# InkTime.net
KiCad netlist of a schematic drawn in EAGLE
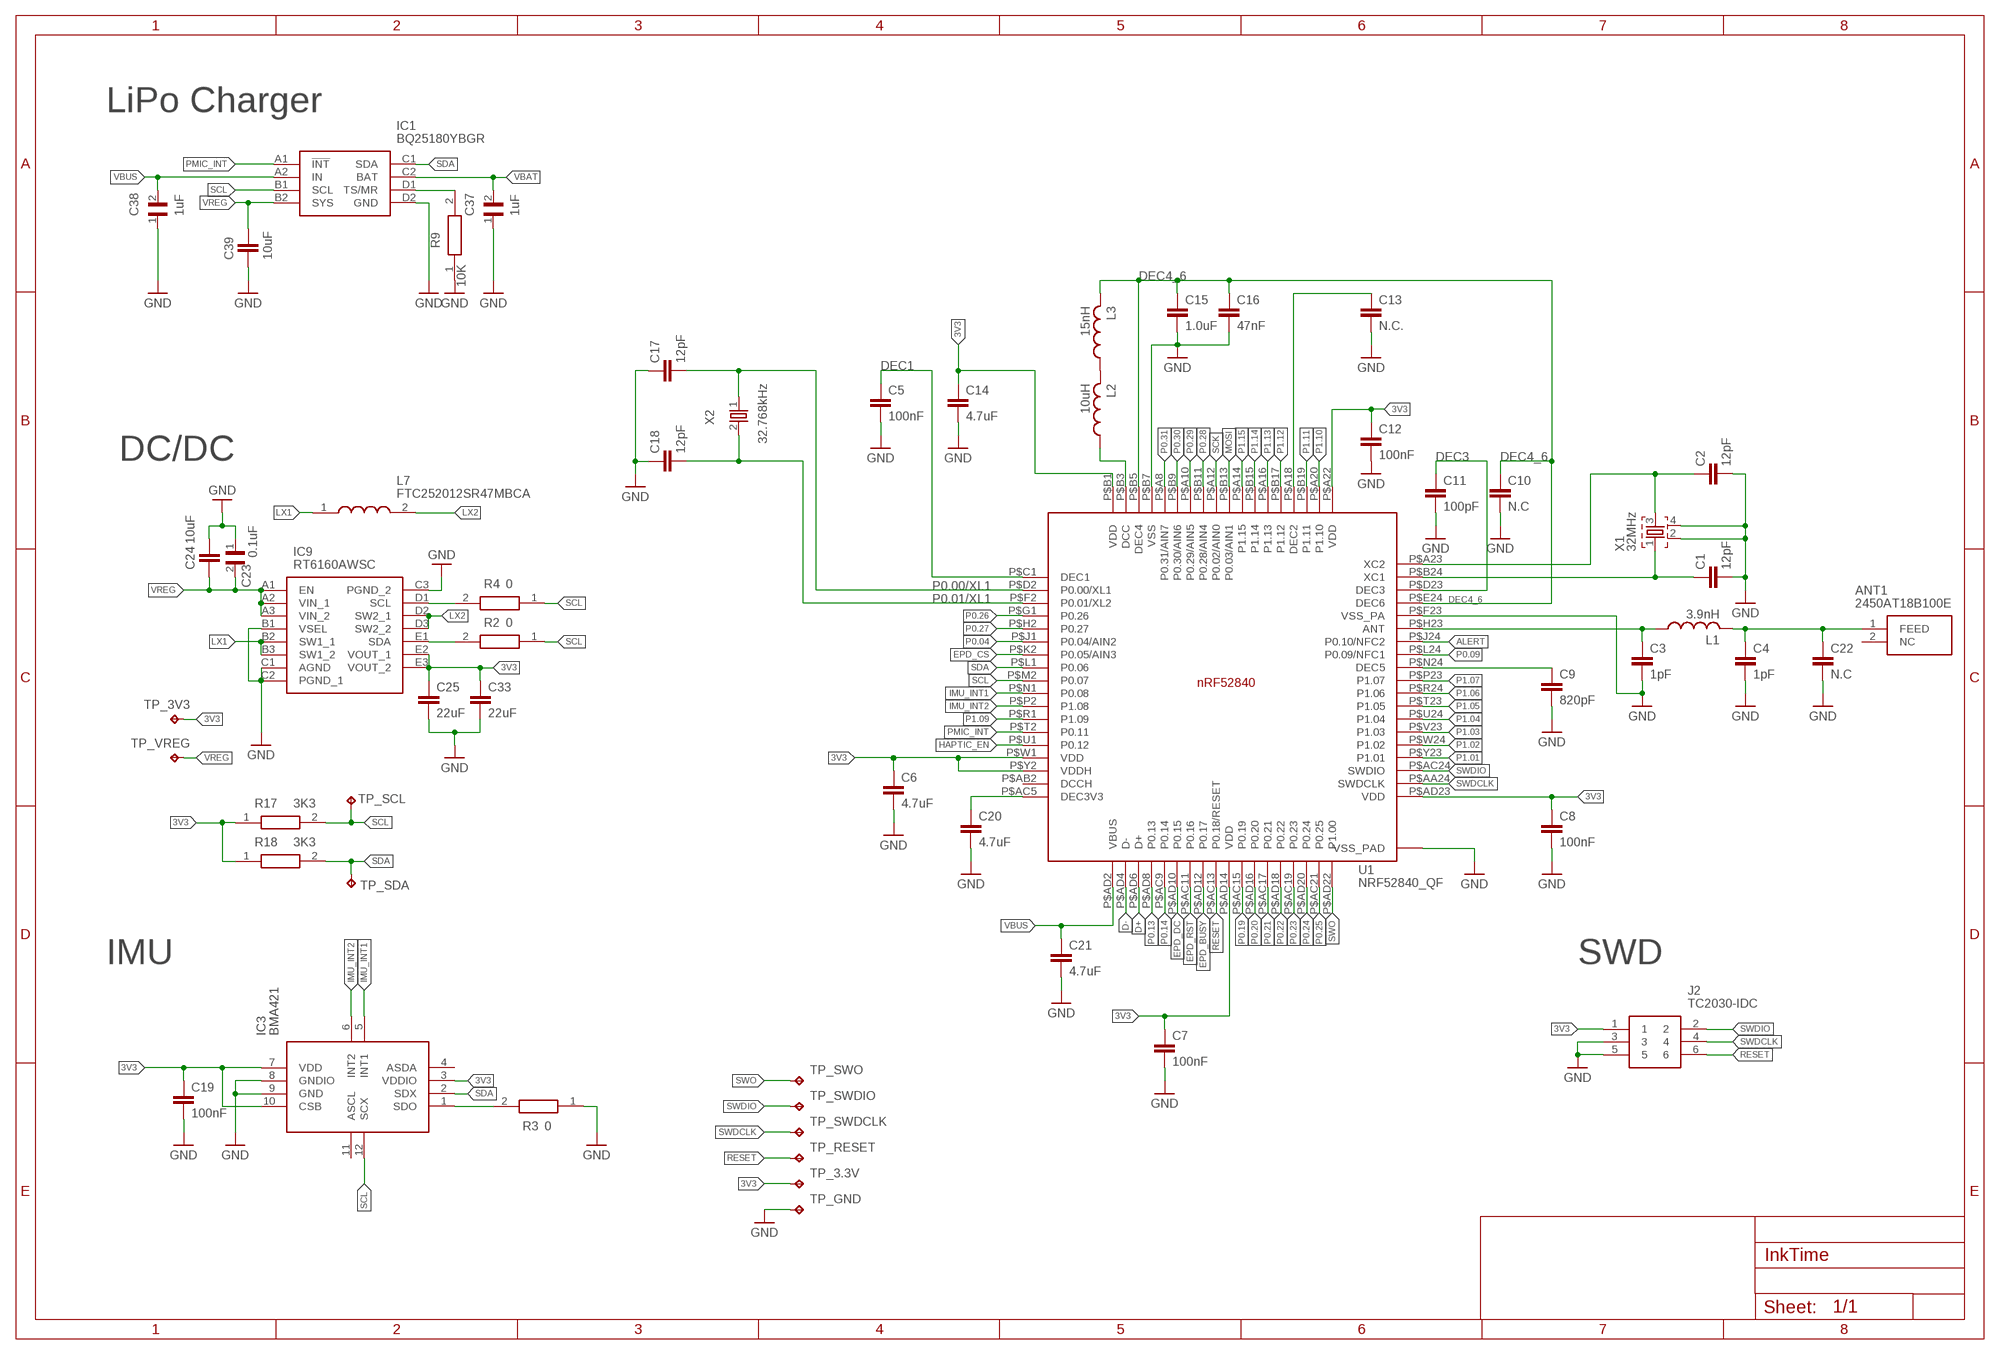
[diagram p0: schematic, sheet 1, part 1 of 2]
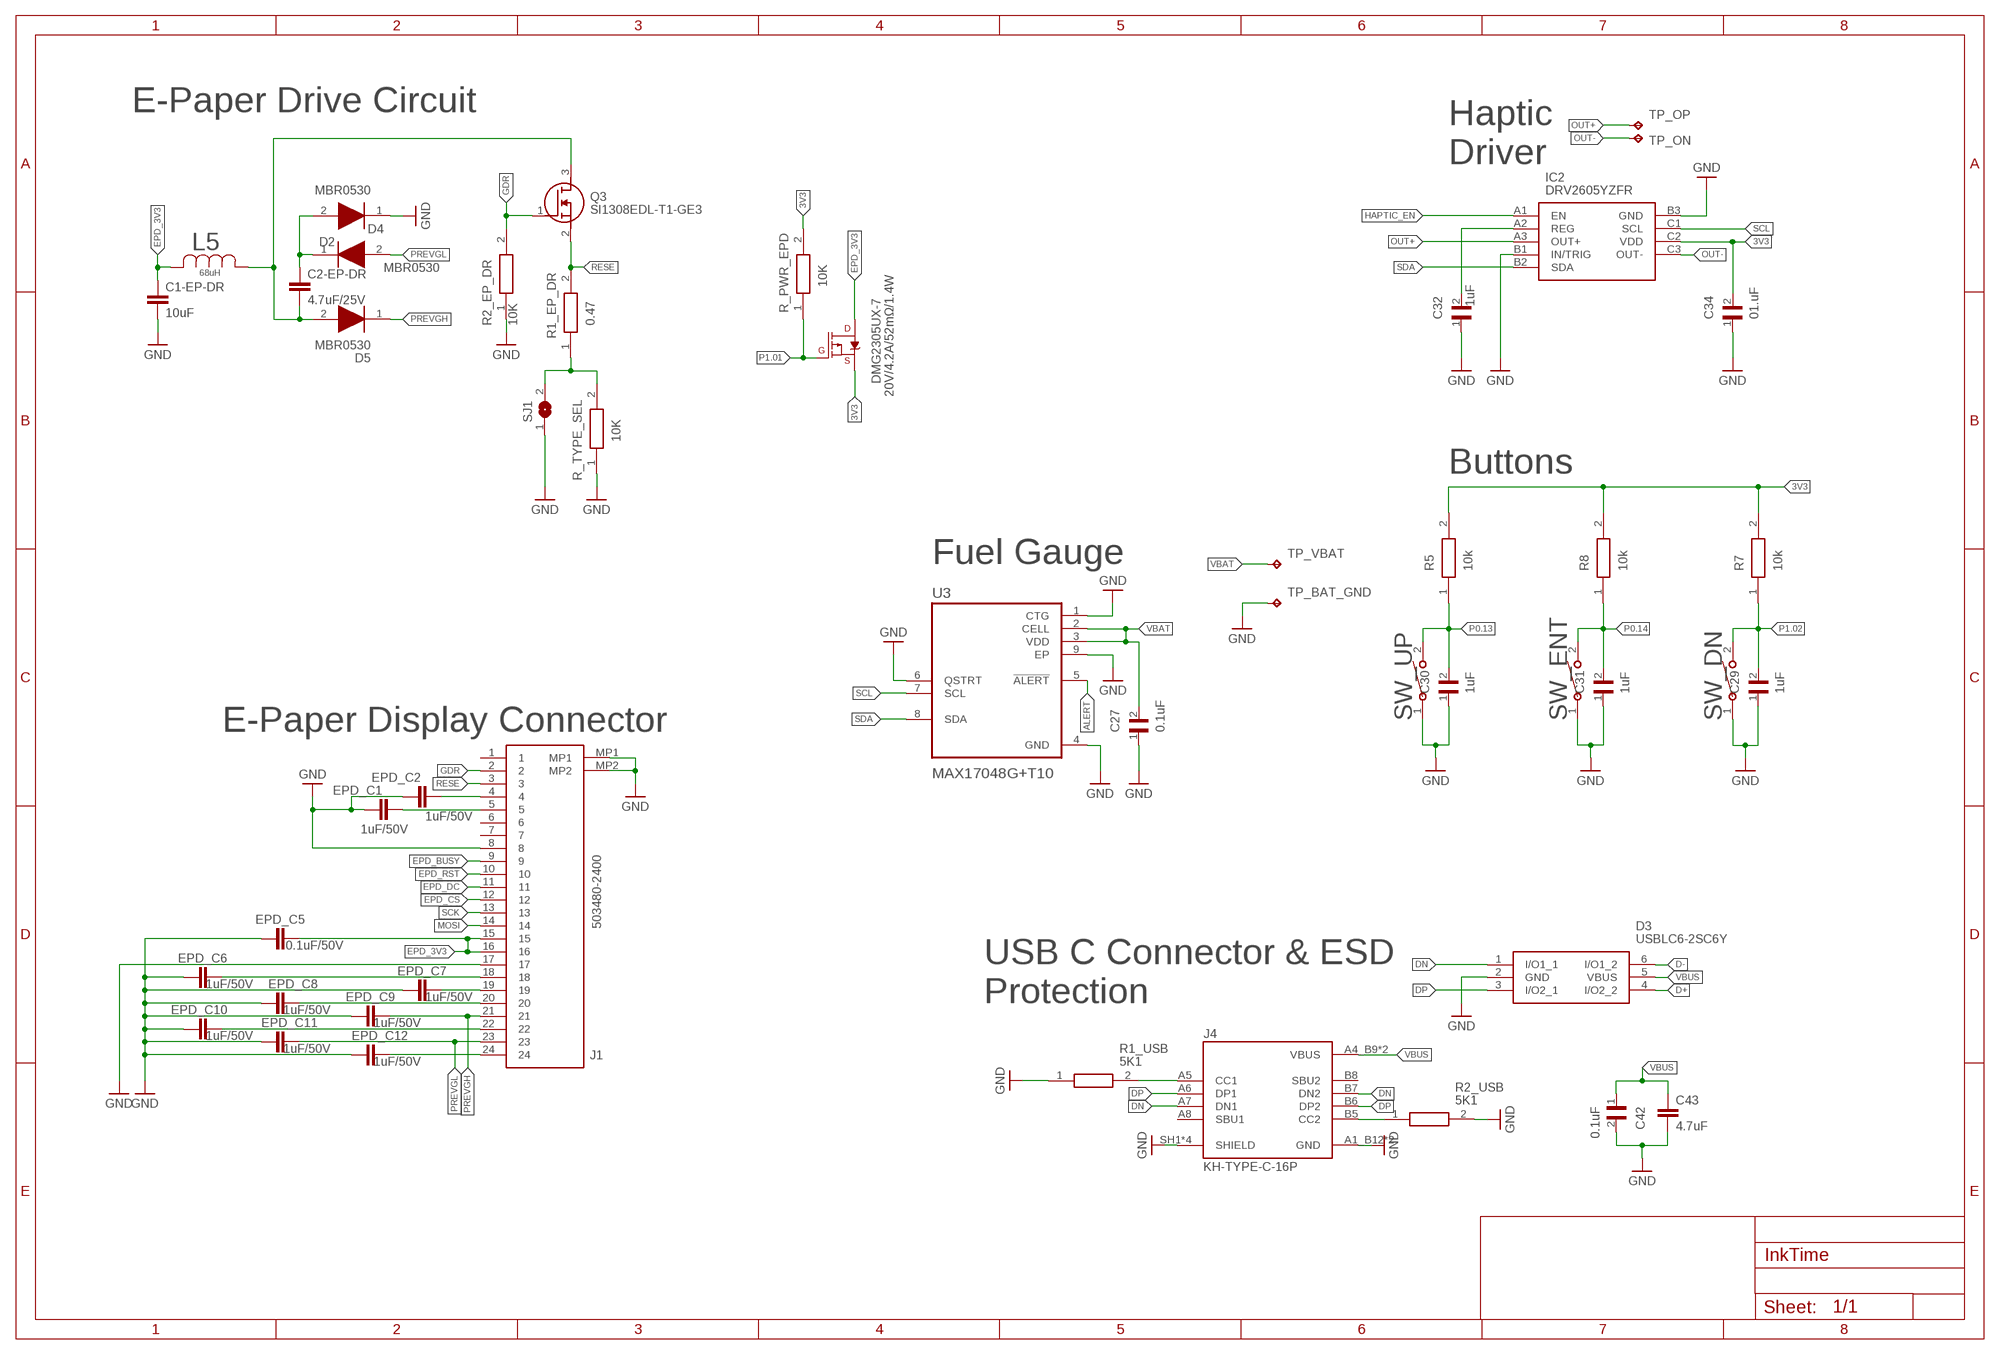
[diagram p1: schematic, sheet 1, part 2 of 2]

(export (version "E")
  (design (tool "Eeschema 10.0.6"))
  (components
    (comp (ref "ANT1")
      (value "2450AT18B100E")
      (footprint "eagle-import:2450AT18B100E_ANTC3216X140N")
      (fields (field (name "MOUSER_PART_NUMBER") "609-2450AT18B100E"))
      (libsource (lib "eagle-import") (part "2450AT18B100E_2450AT18B100E"))
    )
    (comp (ref "C1")
      (value "12pF")
      (footprint "eagle-import:NORDIC_NRF_3_RESC0201_L")
      (libsource (lib "eagle-import") (part "NORDIC_NRF_3_CAPACITOR_0201_L"))
    )
    (comp (ref "C1-EP-DR")
      (value "10uF")
      (footprint "eagle-import:NORDIC_NRF_3_RESC0402_M")
      (libsource (lib "eagle-import") (part "NORDIC_NRF_3_CAPACITOR_0402_M"))
    )
    (comp (ref "C2")
      (value "12pF")
      (footprint "eagle-import:NORDIC_NRF_3_RESC0201_L")
      (libsource (lib "eagle-import") (part "NORDIC_NRF_3_CAPACITOR_0201_L"))
    )
    (comp (ref "C2-EP-DR")
      (value "4.7uF/25V")
      (footprint "eagle-import:NORDIC_NRF_3_RESC0402_M")
      (libsource (lib "eagle-import") (part "NORDIC_NRF_3_CAPACITOR_0402_M"))
    )
    (comp (ref "C3")
      (value "1pF")
      (footprint "eagle-import:NORDIC_NRF_3_RESC0201_L")
      (libsource (lib "eagle-import") (part "NORDIC_NRF_3_CAPACITOR_0201_L"))
    )
    (comp (ref "C4")
      (value "1pF")
      (footprint "eagle-import:NORDIC_NRF_3_RESC0201_L")
      (libsource (lib "eagle-import") (part "NORDIC_NRF_3_CAPACITOR_0201_L"))
    )
    (comp (ref "C5")
      (value "100nF")
      (footprint "eagle-import:NORDIC_NRF_3_RESC0201_L")
      (libsource (lib "eagle-import") (part "NORDIC_NRF_3_CAPACITOR_0201_L"))
    )
    (comp (ref "C6")
      (value "4.7uF")
      (footprint "eagle-import:NORDIC_NRF_3_RESC0402_M")
      (libsource (lib "eagle-import") (part "NORDIC_NRF_3_CAPACITOR_0402_M"))
    )
    (comp (ref "C7")
      (value "100nF")
      (footprint "eagle-import:NORDIC_NRF_3_RESC0201_L")
      (libsource (lib "eagle-import") (part "NORDIC_NRF_3_CAPACITOR_0201_L"))
    )
    (comp (ref "C8")
      (value "100nF")
      (footprint "eagle-import:NORDIC_NRF_3_RESC0201_L")
      (libsource (lib "eagle-import") (part "NORDIC_NRF_3_CAPACITOR_0201_L"))
    )
    (comp (ref "C9")
      (value "820pF")
      (footprint "eagle-import:NORDIC_NRF_3_RESC0201_L")
      (libsource (lib "eagle-import") (part "NORDIC_NRF_3_CAPACITOR_0201_L"))
    )
    (comp (ref "C10")
      (value "N.C")
      (footprint "eagle-import:NORDIC_NRF_3_RESC0201_L")
      (libsource (lib "eagle-import") (part "NORDIC_NRF_3_CAPACITOR_0201_L"))
    )
    (comp (ref "C11")
      (value "100pF")
      (footprint "eagle-import:NORDIC_NRF_3_RESC0201_L")
      (libsource (lib "eagle-import") (part "NORDIC_NRF_3_CAPACITOR_0201_L"))
    )
    (comp (ref "C12")
      (value "100nF")
      (footprint "eagle-import:NORDIC_NRF_3_RESC0201_L")
      (libsource (lib "eagle-import") (part "NORDIC_NRF_3_CAPACITOR_0201_L"))
    )
    (comp (ref "C13")
      (value "N.C.")
      (footprint "eagle-import:NORDIC_NRF_3_RESC0201_L")
      (libsource (lib "eagle-import") (part "NORDIC_NRF_3_CAPACITOR_0201_L"))
    )
    (comp (ref "C14")
      (value "4.7uF")
      (footprint "eagle-import:NORDIC_NRF_3_RESC0402_M")
      (libsource (lib "eagle-import") (part "NORDIC_NRF_3_CAPACITOR_0402_M"))
    )
    (comp (ref "C15")
      (value "1.0uF")
      (footprint "eagle-import:NORDIC_NRF_3_RESC0402_M")
      (libsource (lib "eagle-import") (part "NORDIC_NRF_3_CAPACITOR_0402_M"))
    )
    (comp (ref "C16")
      (value "47nF")
      (footprint "eagle-import:NORDIC_NRF_3_RESC0201_L")
      (libsource (lib "eagle-import") (part "NORDIC_NRF_3_CAPACITOR_0201_L"))
    )
    (comp (ref "C17")
      (value "12pF")
      (footprint "eagle-import:NORDIC_NRF_3_RESC0201_L")
      (libsource (lib "eagle-import") (part "NORDIC_NRF_3_CAPACITOR_0201_L"))
    )
    (comp (ref "C18")
      (value "12pF")
      (footprint "eagle-import:NORDIC_NRF_3_RESC0201_L")
      (libsource (lib "eagle-import") (part "NORDIC_NRF_3_CAPACITOR_0201_L"))
    )
    (comp (ref "C19")
      (value "100nF")
      (footprint "eagle-import:NORDIC_NRF_3_RESC0201_L")
      (libsource (lib "eagle-import") (part "NORDIC_NRF_3_CAPACITOR_0201_L"))
    )
    (comp (ref "C20")
      (value "4.7uF")
      (footprint "eagle-import:NORDIC_NRF_3_RESC0402_M")
      (libsource (lib "eagle-import") (part "NORDIC_NRF_3_CAPACITOR_0402_M"))
    )
    (comp (ref "C21")
      (value "4.7uF")
      (footprint "eagle-import:NORDIC_NRF_3_RESC0402_M")
      (libsource (lib "eagle-import") (part "NORDIC_NRF_3_CAPACITOR_0402_M"))
    )
    (comp (ref "C22")
      (value "N.C")
      (footprint "eagle-import:NORDIC_NRF_3_RESC0201_L")
      (libsource (lib "eagle-import") (part "NORDIC_NRF_3_CAPACITOR_0201_L"))
    )
    (comp (ref "C23")
      (value "0.1uF")
      (footprint "eagle-import:GRM011R60J152KE01L_2_CAPC0201X13N")
      (fields (field (name "MF") "Murata") (field (name "MP") "GRM011R60J152KE01L"))
      (libsource (lib "eagle-import") (part "GRM011R60J152KE01L_2_GRM011R60J152KE01L"))
    )
    (comp (ref "C24")
      (value "10uF")
      (footprint "eagle-import:NORDIC_NRF_3_RESC0402_M")
      (libsource (lib "eagle-import") (part "NORDIC_NRF_3_CAPACITOR_0402_M"))
    )
    (comp (ref "C25")
      (value "22uF")
      (footprint "eagle-import:NORDIC_NRF_3_RESC0402_M")
      (libsource (lib "eagle-import") (part "NORDIC_NRF_3_CAPACITOR_0402_M"))
    )
    (comp (ref "C27")
      (value "0.1uF")
      (footprint "eagle-import:GRM011R60J152KE01L_1_0201")
      (libsource (lib "eagle-import") (part "GRM011R60J152KE01L_1_GRM011R60J152KE01L"))
    )
    (comp (ref "C29")
      (value "1uF")
      (footprint "eagle-import:GRM011R60J152KE01L_1_0201")
      (libsource (lib "eagle-import") (part "GRM011R60J152KE01L_1_GRM011R60J152KE01L"))
    )
    (comp (ref "C30")
      (value "1uF")
      (footprint "eagle-import:GRM011R60J152KE01L_1_0201")
      (libsource (lib "eagle-import") (part "GRM011R60J152KE01L_1_GRM011R60J152KE01L"))
    )
    (comp (ref "C31")
      (value "1uF")
      (footprint "eagle-import:GRM011R60J152KE01L_1_0201")
      (libsource (lib "eagle-import") (part "GRM011R60J152KE01L_1_GRM011R60J152KE01L"))
    )
    (comp (ref "C32")
      (value "1uF")
      (footprint "eagle-import:GRM011R60J152KE01L_1_0201")
      (libsource (lib "eagle-import") (part "GRM011R60J152KE01L_1_GRM011R60J152KE01L"))
    )
    (comp (ref "C33")
      (value "22uF")
      (footprint "eagle-import:NORDIC_NRF_3_RESC0402_M")
      (libsource (lib "eagle-import") (part "NORDIC_NRF_3_CAPACITOR_0402_M"))
    )
    (comp (ref "C34")
      (value "01.uF")
      (footprint "eagle-import:GRM011R60J152KE01L_1_0201")
      (libsource (lib "eagle-import") (part "GRM011R60J152KE01L_1_GRM011R60J152KE01L"))
    )
    (comp (ref "C37")
      (value "1uF")
      (footprint "eagle-import:GRM011R60J152KE01L_2_CAPC0201X13N")
      (fields (field (name "MF") "Murata") (field (name "MP") "GRM011R60J152KE01L"))
      (libsource (lib "eagle-import") (part "GRM011R60J152KE01L_2_GRM011R60J152KE01L"))
    )
    (comp (ref "C38")
      (value "1uF")
      (footprint "eagle-import:GRM011R60J152KE01L_2_CAPC0201X13N")
      (fields (field (name "MF") "Murata") (field (name "MP") "GRM011R60J152KE01L"))
      (libsource (lib "eagle-import") (part "GRM011R60J152KE01L_2_GRM011R60J152KE01L"))
    )
    (comp (ref "C39")
      (value "10uF")
      (footprint "eagle-import:NORDIC_NRF_3_RESC0402_M")
      (libsource (lib "eagle-import") (part "NORDIC_NRF_3_CAPACITOR_0402_M"))
    )
    (comp (ref "C42")
      (value "0.1uF")
      (footprint "eagle-import:GRM011R60J152KE01L_1_0201")
      (libsource (lib "eagle-import") (part "GRM011R60J152KE01L_1_GRM011R60J152KE01L"))
    )
    (comp (ref "C43")
      (value "4.7uF")
      (footprint "eagle-import:NORDIC_NRF_3_RESC0402_M")
      (libsource (lib "eagle-import") (part "NORDIC_NRF_3_CAPACITOR_0402_M"))
    )
    (comp (ref "D2")
      (value "MBR0530")
      (footprint "eagle-import:ESP32_C6_LIBRARY_5_SOD3716X135N")
      (fields (field (name "MF") "ON Semiconductor"))
      (libsource (lib "eagle-import") (part "ESP32_C6_LIBRARY_5_MBR0530"))
    )
    (comp (ref "D3")
      (value "USBLC6-2SC6Y")
      (footprint "eagle-import:ESP32_C6_LIBRARY_3_SOT95P280X145-6N")
      (fields (field (name "MF") "STMicroelectronics"))
      (libsource (lib "eagle-import") (part "ESP32_C6_LIBRARY_3_USBLC6-2SC6Y"))
    )
    (comp (ref "D4")
      (value "MBR0530")
      (footprint "eagle-import:ESP32_C6_LIBRARY_5_SOD3716X135N")
      (fields (field (name "MF") "ON Semiconductor"))
      (libsource (lib "eagle-import") (part "ESP32_C6_LIBRARY_5_MBR0530"))
    )
    (comp (ref "D5")
      (value "MBR0530")
      (footprint "eagle-import:ESP32_C6_LIBRARY_5_SOD3716X135N")
      (fields (field (name "MF") "ON Semiconductor"))
      (libsource (lib "eagle-import") (part "ESP32_C6_LIBRARY_5_MBR0530"))
    )
    (comp (ref "DMG2305UX-7")
      (value "20V/4.2A/52mΩ/1.4W")
      (footprint "eagle-import:ESP32_C6_LIBRARY_4_ESP32_C6_LIBRARY_4_ESP32_C6_LIBRARY_4_ESP32_C6_LIBRARY_4_ESP32_WROVER_SPARKFUN-DISCRETESEMI_SOT23-3")
      (libsource (lib "eagle-import") (part "ESP32_C6_LIBRARY_4_ESP32_WROVER_SPARKFUN-DISCRETESEMI_MOSFET_PCH-DMG2305UX-7"))
    )
    (comp (ref "EPD_C1")
      (value "1uF/50V")
      (footprint "eagle-import:NORDIC_NRF_3_RESC0402_M")
      (libsource (lib "eagle-import") (part "NORDIC_NRF_3_CAPACITOR_0402_M"))
    )
    (comp (ref "EPD_C2")
      (value "1uF/50V")
      (footprint "eagle-import:NORDIC_NRF_3_RESC0402_M")
      (libsource (lib "eagle-import") (part "NORDIC_NRF_3_CAPACITOR_0402_M"))
    )
    (comp (ref "EPD_C5")
      (value "0.1uF/50V")
      (footprint "eagle-import:NORDIC_NRF_3_RESC0201_L")
      (libsource (lib "eagle-import") (part "NORDIC_NRF_3_CAPACITOR_0201_L"))
    )
    (comp (ref "EPD_C6")
      (value "1uF/50V")
      (footprint "eagle-import:NORDIC_NRF_3_RESC0402_M")
      (libsource (lib "eagle-import") (part "NORDIC_NRF_3_CAPACITOR_0402_M"))
    )
    (comp (ref "EPD_C7")
      (value "1uF/50V")
      (footprint "eagle-import:NORDIC_NRF_3_RESC0402_M")
      (libsource (lib "eagle-import") (part "NORDIC_NRF_3_CAPACITOR_0402_M"))
    )
    (comp (ref "EPD_C8")
      (value "1uF/50V")
      (footprint "eagle-import:NORDIC_NRF_3_RESC0402_M")
      (libsource (lib "eagle-import") (part "NORDIC_NRF_3_CAPACITOR_0402_M"))
    )
    (comp (ref "EPD_C9")
      (value "1uF/50V")
      (footprint "eagle-import:NORDIC_NRF_3_RESC0402_M")
      (libsource (lib "eagle-import") (part "NORDIC_NRF_3_CAPACITOR_0402_M"))
    )
    (comp (ref "EPD_C10")
      (value "1uF/50V")
      (footprint "eagle-import:NORDIC_NRF_3_RESC0402_M")
      (libsource (lib "eagle-import") (part "NORDIC_NRF_3_CAPACITOR_0402_M"))
    )
    (comp (ref "EPD_C11")
      (value "1uF/50V")
      (footprint "eagle-import:NORDIC_NRF_3_RESC0402_M")
      (libsource (lib "eagle-import") (part "NORDIC_NRF_3_CAPACITOR_0402_M"))
    )
    (comp (ref "EPD_C12")
      (value "1uF/50V")
      (footprint "eagle-import:NORDIC_NRF_3_RESC0402_M")
      (libsource (lib "eagle-import") (part "NORDIC_NRF_3_CAPACITOR_0402_M"))
    )
    (comp (ref "IC1")
      (value "BQ25180YBGR")
      (footprint "eagle-import:BQ25180YBGR_BGA8C40P2X4_100X155X50")
      (fields (field (name "MOUSER_PART_NUMBER") "595-BQ25180YBGR"))
      (libsource (lib "eagle-import") (part "BQ25180YBGR_BQ25180YBGR"))
    )
    (comp (ref "IC2")
      (value "DRV2605YZFR")
      (footprint "eagle-import:DRV2605YZFR_BGA9C50P3X3_144X144X62")
      (libsource (lib "eagle-import") (part "DRV2605YZFR_DRV2605YZFR"))
    )
    (comp (ref "IC3")
      (value "BMA421")
      (footprint "eagle-import:BMA423_BMA423")
      (fields (field (name "ARROW_PART_NUMBER") "BMA423") (field (name "MOUSER_PART_NUMBER") "262-BMA423"))
      (libsource (lib "eagle-import") (part "BMA423_BMA423"))
    )
    (comp (ref "IC9")
      (value "RT6160AWSC")
      (footprint "eagle-import:RT6160AWSC_BGA15C40P3X5_140X230X60")
      (fields (field (name "MOUSER_PART_NUMBER") "835-RT6160AWSC"))
      (libsource (lib "eagle-import") (part "RT6160AWSC_RT6160AWSC"))
    )
    (comp (ref "J1")
      (value "503480-2400")
      (footprint "eagle-import:503480-2400_5034802400")
      (fields (field (name "MOUSER_PART_NUMBER") "538-503480-2400"))
      (libsource (lib "eagle-import") (part "503480-2400_503480-2400"))
    )
    (comp (ref "J2")
      (value "TC2030-IDC")
      (footprint "eagle-import:TC2030-IDC_TC2030IDC")
      (libsource (lib "eagle-import") (part "TC2030-IDC_TC2030-IDC"))
    )
    (comp (ref "J4")
      (value "KH-TYPE-C-16P")
      (footprint "eagle-import:KH-TYPE-C-16P_KINGHELM_KH-TYPE-C-16P")
      (fields (field (name "MF") "kinghelm"))
      (libsource (lib "eagle-import") (part "KH-TYPE-C-16P_KH-TYPE-C-16P"))
    )
    (comp (ref "L1")
      (value "3.9nH")
      (footprint "eagle-import:NORDIC_NRF_2_RESC0201_M")
      (libsource (lib "eagle-import") (part "NORDIC_NRF_2_INDUCTOR_0201_M"))
    )
    (comp (ref "L2")
      (value "10uH")
      (footprint "eagle-import:NORDIC_NRF_2_RESC0201_M")
      (libsource (lib "eagle-import") (part "NORDIC_NRF_2_INDUCTOR_0201_M"))
    )
    (comp (ref "L3")
      (value "15nH")
      (footprint "eagle-import:NORDIC_NRF_2_RESC0201_M")
      (libsource (lib "eagle-import") (part "NORDIC_NRF_2_INDUCTOR_0201_M"))
    )
    (comp (ref "L5")
      (value "68uH")
      (footprint "eagle-import:ESP32_C6_LIBRARY_2_IND_4828-WE-TPC_WRE")
      (fields
        (field (name "MANUFACTURER_PART_NUMBER") "744043680")
        (field (name "COPYRIGHT") "Copyright (C) 2024 Ultra Librarian. All rights reserved.")
      )
      (libsource (lib "eagle-import") (part "ESP32_C6_LIBRARY_2_744043680IND_4828-WE-TPC_WRE"))
    )
    (comp (ref "L7")
      (value "FTC252012SR47MBCA")
      (footprint "eagle-import:MLP2016SR47MT0S1_INDC2016X100N")
      (libsource (lib "eagle-import") (part "MLP2016SR47MT0S1_FTC252012SR47MBCA"))
    )
    (comp (ref "Q3")
      (value "SI1308EDL-T1-GE3")
      (footprint "eagle-import:ESP32_C6_LIBRARY_6_SOT65P210X110-3N")
      (fields (field (name "MF") "Vishay Siliconix"))
      (libsource (lib "eagle-import") (part "ESP32_C6_LIBRARY_6_SI1308EDL-T1-GE3"))
    )
    (comp (ref "R1_EP_DR")
      (value "0.47")
      (footprint "eagle-import:ERA-1AEB3401C_0201")
      (libsource (lib "eagle-import") (part "ERA-1AEB3401C_CPF0201D7K68C1"))
    )
    (comp (ref "R1_USB")
      (value "5K1")
      (footprint "eagle-import:ERA-1AEB3401C_0201")
      (libsource (lib "eagle-import") (part "ERA-1AEB3401C_CPF0201D7K68C1"))
    )
    (comp (ref "R2")
      (value "0")
      (footprint "eagle-import:ERA-1AEB3401C_0201")
      (libsource (lib "eagle-import") (part "ERA-1AEB3401C_CPF0201D7K68C1"))
    )
    (comp (ref "R2_EP_DR")
      (value "10K")
      (footprint "eagle-import:ERA-1AEB3401C_0201")
      (libsource (lib "eagle-import") (part "ERA-1AEB3401C_CPF0201D7K68C1"))
    )
    (comp (ref "R2_USB")
      (value "5K1")
      (footprint "eagle-import:ERA-1AEB3401C_0201")
      (libsource (lib "eagle-import") (part "ERA-1AEB3401C_CPF0201D7K68C1"))
    )
    (comp (ref "R3")
      (value "0")
      (footprint "eagle-import:ERA-1AEB3401C_0201")
      (libsource (lib "eagle-import") (part "ERA-1AEB3401C_CPF0201D7K68C1"))
    )
    (comp (ref "R4")
      (value "0")
      (footprint "eagle-import:ERA-1AEB3401C_0201")
      (libsource (lib "eagle-import") (part "ERA-1AEB3401C_CPF0201D7K68C1"))
    )
    (comp (ref "R5")
      (value "10k")
      (footprint "eagle-import:ERA-1AEB3401C_0201")
      (libsource (lib "eagle-import") (part "ERA-1AEB3401C_CPF0201D7K68C1"))
    )
    (comp (ref "R7")
      (value "10k")
      (footprint "eagle-import:ERA-1AEB3401C_0201")
      (libsource (lib "eagle-import") (part "ERA-1AEB3401C_CPF0201D7K68C1"))
    )
    (comp (ref "R8")
      (value "10k")
      (footprint "eagle-import:ERA-1AEB3401C_0201")
      (libsource (lib "eagle-import") (part "ERA-1AEB3401C_CPF0201D7K68C1"))
    )
    (comp (ref "R9")
      (value "10K")
      (footprint "eagle-import:ERA-1AEB3401C_0201")
      (libsource (lib "eagle-import") (part "ERA-1AEB3401C_CPF0201D7K68C1"))
    )
    (comp (ref "R17")
      (value "3K3")
      (footprint "eagle-import:ERA-1AEB3401C_0201")
      (libsource (lib "eagle-import") (part "ERA-1AEB3401C_CPF0201D7K68C1"))
    )
    (comp (ref "R18")
      (value "3K3")
      (footprint "eagle-import:ERA-1AEB3401C_0201")
      (libsource (lib "eagle-import") (part "ERA-1AEB3401C_CPF0201D7K68C1"))
    )
    (comp (ref "R_PWR_EPD")
      (value "10K")
      (footprint "eagle-import:ERA-1AEB3401C_0201")
      (libsource (lib "eagle-import") (part "ERA-1AEB3401C_CPF0201D7K68C1"))
    )
    (comp (ref "R_TYPE_SEL")
      (value "10K")
      (footprint "eagle-import:ERA-1AEB3401C_0201")
      (libsource (lib "eagle-import") (part "ERA-1AEB3401C_CPF0201D7K68C1"))
    )
    (comp (ref "SJ1")
      (value "ESP32_C6_LIBRARY_7_JUMPER_SJ")
      (footprint "eagle-import:ESP32_C6_LIBRARY_7_JUMPER_SJ")
      (libsource (lib "eagle-import") (part "ESP32_C6_LIBRARY_7_JUMPER_SJ"))
    )
    (comp (ref "SW_DN")
      (value "2025-10-22_07-23-44_LIBRARY_EVP-AKE31ASW_EVP-AKE31A_PAN")
      (footprint "eagle-import:2025-10-22_07-23-44_LIBRARY_SW_EVP-AKE31A_PAN")
      (fields
        (field (name "MANUFACTURER_PART_NUMBER") "EVP-AKE31A")
        (field (name "COPYRIGHT") "Copyright (C) 2025 Ultra Librarian. All rights reserved.")
      )
      (libsource (lib "eagle-import") (part "2025-10-22_07-23-44_LIBRARY_EVP-AKE31ASW_EVP-AKE31A_PAN"))
    )
    (comp (ref "SW_ENT")
      (value "2025-10-22_07-23-44_LIBRARY_EVP-AKE31ASW_EVP-AKE31A_PAN")
      (footprint "eagle-import:2025-10-22_07-23-44_LIBRARY_SW_EVP-AKE31A_PAN")
      (fields
        (field (name "MANUFACTURER_PART_NUMBER") "EVP-AKE31A")
        (field (name "COPYRIGHT") "Copyright (C) 2025 Ultra Librarian. All rights reserved.")
      )
      (libsource (lib "eagle-import") (part "2025-10-22_07-23-44_LIBRARY_EVP-AKE31ASW_EVP-AKE31A_PAN"))
    )
    (comp (ref "SW_UP")
      (value "2025-10-22_07-23-44_LIBRARY_EVP-AKE31ASW_EVP-AKE31A_PAN")
      (footprint "eagle-import:2025-10-22_07-23-44_LIBRARY_SW_EVP-AKE31A_PAN")
      (fields
        (field (name "MANUFACTURER_PART_NUMBER") "EVP-AKE31A")
        (field (name "COPYRIGHT") "Copyright (C) 2025 Ultra Librarian. All rights reserved.")
      )
      (libsource (lib "eagle-import") (part "2025-10-22_07-23-44_LIBRARY_EVP-AKE31ASW_EVP-AKE31A_PAN"))
    )
    (comp (ref "TP_3.3V")
      (value "HECTOR_WATCH_1_TPTP20R")
      (footprint "eagle-import:HECTOR_WATCH_1_TP20R")
      (libsource (lib "eagle-import") (part "HECTOR_WATCH_1_TPTP20R"))
    )
    (comp (ref "TP_3V3")
      (value "HECTOR_WATCH_1_TPTP20R")
      (footprint "eagle-import:HECTOR_WATCH_1_TP20R")
      (libsource (lib "eagle-import") (part "HECTOR_WATCH_1_TPTP20R"))
    )
    (comp (ref "TP_BAT_GND")
      (value "HECTOR_WATCH_1_TPTP20R")
      (footprint "eagle-import:HECTOR_WATCH_1_TP20R")
      (libsource (lib "eagle-import") (part "HECTOR_WATCH_1_TPTP20R"))
    )
    (comp (ref "TP_GND")
      (value "HECTOR_WATCH_1_TPTP20R")
      (footprint "eagle-import:HECTOR_WATCH_1_TP20R")
      (libsource (lib "eagle-import") (part "HECTOR_WATCH_1_TPTP20R"))
    )
    (comp (ref "TP_ON")
      (value "HECTOR_WATCH_1_TPTP20R")
      (footprint "eagle-import:HECTOR_WATCH_1_TP20R")
      (libsource (lib "eagle-import") (part "HECTOR_WATCH_1_TPTP20R"))
    )
    (comp (ref "TP_OP")
      (value "HECTOR_WATCH_1_TPTP20R")
      (footprint "eagle-import:HECTOR_WATCH_1_TP20R")
      (libsource (lib "eagle-import") (part "HECTOR_WATCH_1_TPTP20R"))
    )
    (comp (ref "TP_RESET")
      (value "HECTOR_WATCH_1_TPTP20R")
      (footprint "eagle-import:HECTOR_WATCH_1_TP20R")
      (libsource (lib "eagle-import") (part "HECTOR_WATCH_1_TPTP20R"))
    )
    (comp (ref "TP_SCL")
      (value "HECTOR_WATCH_1_TPTP20R")
      (footprint "eagle-import:HECTOR_WATCH_1_TP20R")
      (libsource (lib "eagle-import") (part "HECTOR_WATCH_1_TPTP20R"))
    )
    (comp (ref "TP_SDA")
      (value "HECTOR_WATCH_1_TPTP20R")
      (footprint "eagle-import:HECTOR_WATCH_1_TP20R")
      (libsource (lib "eagle-import") (part "HECTOR_WATCH_1_TPTP20R"))
    )
    (comp (ref "TP_SWDCLK")
      (value "HECTOR_WATCH_1_TPTP20R")
      (footprint "eagle-import:HECTOR_WATCH_1_TP20R")
      (libsource (lib "eagle-import") (part "HECTOR_WATCH_1_TPTP20R"))
    )
    (comp (ref "TP_SWDIO")
      (value "HECTOR_WATCH_1_TPTP20R")
      (footprint "eagle-import:HECTOR_WATCH_1_TP20R")
      (libsource (lib "eagle-import") (part "HECTOR_WATCH_1_TPTP20R"))
    )
    (comp (ref "TP_SWO")
      (value "HECTOR_WATCH_1_TPTP20R")
      (footprint "eagle-import:HECTOR_WATCH_1_TP20R")
      (libsource (lib "eagle-import") (part "HECTOR_WATCH_1_TPTP20R"))
    )
    (comp (ref "TP_VBAT")
      (value "HECTOR_WATCH_1_TPTP20R")
      (footprint "eagle-import:HECTOR_WATCH_1_TP20R")
      (libsource (lib "eagle-import") (part "HECTOR_WATCH_1_TPTP20R"))
    )
    (comp (ref "TP_VREG")
      (value "HECTOR_WATCH_1_TPTP20R")
      (footprint "eagle-import:HECTOR_WATCH_1_TP20R")
      (libsource (lib "eagle-import") (part "HECTOR_WATCH_1_TPTP20R"))
    )
    (comp (ref "U1")
      (value "NRF52840_QF")
      (footprint "eagle-import:NORDIC_NRF_4_AQFN50P700X700X85_HS-74N")
      (libsource (lib "eagle-import") (part "NORDIC_NRF_4_NRF52840_QF"))
    )
    (comp (ref "U3")
      (value "MAX17048G+T10")
      (footprint "eagle-import:ESP32_C6_LIBRARY_SON50P200X200X80-9N")
      (fields (field (name "MF") "Analog Devices"))
      (libsource (lib "eagle-import") (part "ESP32_C6_LIBRARY_MAX17048G+T10"))
    )
    (comp (ref "X1")
      (value "32MHz")
      (footprint "eagle-import:NORDIC_NRF_BT-XTAL_2016_N")
      (libsource (lib "eagle-import") (part "NORDIC_NRF_XTAL_32MHZ"))
    )
    (comp (ref "X2")
      (value "32.768kHz")
      (footprint "eagle-import:NORDIC_NRF_1_XTAL_3215_N")
      (libsource (lib "eagle-import") (part "NORDIC_NRF_1_XTAL_32KHZ"))
    )
  )
  (nets
    (net (code "1") (name "3V3") (class "Default")
      (node (ref "C12") (pin "1") (pinfunction "1_1") (pintype "passive"))
      (node (ref "C14") (pin "1") (pinfunction "1_1") (pintype "passive"))
      (node (ref "C19") (pin "1") (pinfunction "1_1") (pintype "passive"))
      (node (ref "C25") (pin "1") (pinfunction "1_1") (pintype "passive"))
      (node (ref "C33") (pin "1") (pinfunction "1_1") (pintype "passive"))
      (node (ref "C34") (pin "2") (pinfunction "2_2") (pintype "passive"))
      (node (ref "C6") (pin "1") (pinfunction "1_1") (pintype "passive"))
      (node (ref "C7") (pin "1") (pinfunction "1_1") (pintype "passive"))
      (node (ref "C8") (pin "1") (pinfunction "1_1") (pintype "passive"))
      (node (ref "DMG2305UX-7") (pin "2") (pinfunction "S_2") (pintype "bidirectional"))
      (node (ref "IC2") (pin "C2") (pinfunction "VDD_C2") (pintype "bidirectional"))
      (node (ref "IC3") (pin "10") (pinfunction "CSB_10") (pintype "bidirectional"))
      (node (ref "IC3") (pin "3") (pinfunction "VDDIO_3") (pintype "bidirectional"))
      (node (ref "IC3") (pin "7") (pinfunction "VDD_7") (pintype "bidirectional"))
      (node (ref "IC9") (pin "E2") (pinfunction "VOUT_1_E2") (pintype "bidirectional"))
      (node (ref "IC9") (pin "E3") (pinfunction "VOUT_2_E3") (pintype "bidirectional"))
      (node (ref "J2") (pin "1") (pinfunction "1_1") (pintype "bidirectional"))
      (node (ref "R17") (pin "1") (pinfunction "1_1") (pintype "bidirectional"))
      (node (ref "R18") (pin "1") (pinfunction "1_1") (pintype "bidirectional"))
      (node (ref "R5") (pin "2") (pinfunction "2_2") (pintype "bidirectional"))
      (node (ref "R7") (pin "2") (pinfunction "2_2") (pintype "bidirectional"))
      (node (ref "R8") (pin "2") (pinfunction "2_2") (pintype "bidirectional"))
      (node (ref "R_PWR_EPD") (pin "2") (pinfunction "2_2") (pintype "bidirectional"))
      (node (ref "TP_3.3V") (pin "TP") (pinfunction "TP_TP") (pintype "input"))
      (node (ref "TP_3V3") (pin "TP") (pinfunction "TP_TP") (pintype "input"))
      (node (ref "U1") (pin "P$A22") (pinfunction "VDD_P$A22") (pintype "power_in"))
      (node (ref "U1") (pin "P$AD14") (pinfunction "VDD_P$AD14") (pintype "power_in"))
      (node (ref "U1") (pin "P$AD23") (pinfunction "VDD_P$AD23") (pintype "power_in"))
      (node (ref "U1") (pin "P$B1") (pinfunction "VDD_P$B1") (pintype "power_in"))
      (node (ref "U1") (pin "P$W1") (pinfunction "VDD_P$W1") (pintype "power_in"))
      (node (ref "U1") (pin "P$Y2") (pinfunction "VDDH_P$Y2") (pintype "power_in"))
    )
    (net (code "2") (name "ALERT") (class "Default")
      (node (ref "U1") (pin "P$J24") (pinfunction "P0.10/NFC2_P$J24") (pintype "bidirectional"))
      (node (ref "U3") (pin "5") (pinfunction "~{ALERT}_5") (pintype "output"))
    )
    (net (code "3") (name "D+") (class "Default")
      (node (ref "D3") (pin "4") (pinfunction "I/O2_2_4") (pintype "bidirectional"))
      (node (ref "U1") (pin "P$AD6") (pinfunction "D+_P$AD6") (pintype "bidirectional"))
    )
    (net (code "4") (name "D-") (class "Default")
      (node (ref "D3") (pin "6") (pinfunction "I/O1_2_6") (pintype "bidirectional"))
      (node (ref "U1") (pin "P$AD4") (pinfunction "D-_P$AD4") (pintype "bidirectional"))
    )
    (net (code "5") (name "DN") (class "Default")
      (node (ref "D3") (pin "1") (pinfunction "I/O1_1_1") (pintype "bidirectional"))
      (node (ref "J4") (pin "A7") (pinfunction "DN1_A7") (pintype "bidirectional"))
      (node (ref "J4") (pin "B7") (pinfunction "DN2_B7") (pintype "bidirectional"))
    )
    (net (code "6") (name "DP") (class "Default")
      (node (ref "D3") (pin "3") (pinfunction "I/O2_1_3") (pintype "bidirectional"))
      (node (ref "J4") (pin "A6") (pinfunction "DP1_A6") (pintype "bidirectional"))
      (node (ref "J4") (pin "B6") (pinfunction "DP2_B6") (pintype "bidirectional"))
    )
    (net (code "7") (name "EPD_3V3") (class "Default")
      (node (ref "C1-EP-DR") (pin "1") (pinfunction "1_1") (pintype "passive"))
      (node (ref "DMG2305UX-7") (pin "3") (pinfunction "D_3") (pintype "bidirectional"))
      (node (ref "EPD_C5") (pin "2") (pinfunction "2_2") (pintype "passive"))
      (node (ref "J1") (pin "15") (pinfunction "15_15") (pintype "bidirectional"))
      (node (ref "J1") (pin "16") (pinfunction "16_16") (pintype "bidirectional"))
      (node (ref "L5") (pin "2") (pinfunction "2_2") (pintype "passive"))
    )
    (net (code "8") (name "EPD_BUSY") (class "Default")
      (node (ref "J1") (pin "9") (pinfunction "9_9") (pintype "bidirectional"))
      (node (ref "U1") (pin "P$AD12") (pinfunction "P0.17_P$AD12") (pintype "bidirectional"))
    )
    (net (code "9") (name "EPD_CS") (class "Default")
      (node (ref "J1") (pin "12") (pinfunction "12_12") (pintype "bidirectional"))
      (node (ref "U1") (pin "P$K2") (pinfunction "P0.05/AIN3_P$K2") (pintype "bidirectional"))
    )
    (net (code "10") (name "EPD_DC") (class "Default")
      (node (ref "J1") (pin "11") (pinfunction "11_11") (pintype "bidirectional"))
      (node (ref "U1") (pin "P$AD10") (pinfunction "P0.15_P$AD10") (pintype "bidirectional"))
    )
    (net (code "11") (name "EPD_RST") (class "Default")
      (node (ref "J1") (pin "10") (pinfunction "10_10") (pintype "bidirectional"))
      (node (ref "U1") (pin "P$AC11") (pinfunction "P0.16_P$AC11") (pintype "bidirectional"))
    )
    (net (code "12") (name "GDR") (class "Default")
      (node (ref "J1") (pin "2") (pinfunction "2_2") (pintype "bidirectional"))
      (node (ref "Q3") (pin "1") (pinfunction "G_1") (pintype "bidirectional"))
      (node (ref "R2_EP_DR") (pin "2") (pinfunction "2_2") (pintype "bidirectional"))
    )
    (net (code "13") (name "GND") (class "Default")
      (node (ref "C1") (pin "2") (pinfunction "2_2") (pintype "passive"))
      (node (ref "C1-EP-DR") (pin "2") (pinfunction "2_2") (pintype "passive"))
      (node (ref "C10") (pin "2") (pinfunction "2_2") (pintype "passive"))
      (node (ref "C11") (pin "2") (pinfunction "2_2") (pintype "passive"))
      (node (ref "C12") (pin "2") (pinfunction "2_2") (pintype "passive"))
      (node (ref "C13") (pin "2") (pinfunction "2_2") (pintype "passive"))
      (node (ref "C14") (pin "2") (pinfunction "2_2") (pintype "passive"))
      (node (ref "C15") (pin "2") (pinfunction "2_2") (pintype "passive"))
      (node (ref "C16") (pin "2") (pinfunction "2_2") (pintype "passive"))
      (node (ref "C17") (pin "1") (pinfunction "1_1") (pintype "passive"))
      (node (ref "C18") (pin "1") (pinfunction "1_1") (pintype "passive"))
      (node (ref "C19") (pin "2") (pinfunction "2_2") (pintype "passive"))
      (node (ref "C2") (pin "2") (pinfunction "2_2") (pintype "passive"))
      (node (ref "C20") (pin "2") (pinfunction "2_2") (pintype "passive"))
      (node (ref "C21") (pin "2") (pinfunction "2_2") (pintype "passive"))
      (node (ref "C22") (pin "2") (pinfunction "2_2") (pintype "passive"))
      (node (ref "C23") (pin "1") (pinfunction "1_1") (pintype "passive"))
      (node (ref "C24") (pin "1") (pinfunction "1_1") (pintype "passive"))
      (node (ref "C25") (pin "2") (pinfunction "2_2") (pintype "passive"))
      (node (ref "C27") (pin "1") (pinfunction "1_1") (pintype "passive"))
      (node (ref "C29") (pin "1") (pinfunction "1_1") (pintype "passive"))
      (node (ref "C3") (pin "2") (pinfunction "2_2") (pintype "passive"))
      (node (ref "C30") (pin "1") (pinfunction "1_1") (pintype "passive"))
      (node (ref "C31") (pin "1") (pinfunction "1_1") (pintype "passive"))
      (node (ref "C32") (pin "1") (pinfunction "1_1") (pintype "passive"))
      (node (ref "C33") (pin "2") (pinfunction "2_2") (pintype "passive"))
      (node (ref "C34") (pin "1") (pinfunction "1_1") (pintype "passive"))
      (node (ref "C37") (pin "1") (pinfunction "1_1") (pintype "passive"))
      (node (ref "C38") (pin "1") (pinfunction "1_1") (pintype "passive"))
      (node (ref "C39") (pin "2") (pinfunction "2_2") (pintype "passive"))
      (node (ref "C4") (pin "2") (pinfunction "2_2") (pintype "passive"))
      (node (ref "C42") (pin "2") (pinfunction "2_2") (pintype "passive"))
      (node (ref "C43") (pin "2") (pinfunction "2_2") (pintype "passive"))
      (node (ref "C5") (pin "2") (pinfunction "2_2") (pintype "passive"))
      (node (ref "C6") (pin "2") (pinfunction "2_2") (pintype "passive"))
      (node (ref "C7") (pin "2") (pinfunction "2_2") (pintype "passive"))
      (node (ref "C8") (pin "2") (pinfunction "2_2") (pintype "passive"))
      (node (ref "C9") (pin "2") (pinfunction "2_2") (pintype "passive"))
      (node (ref "D3") (pin "2") (pinfunction "GND_2") (pintype "bidirectional"))
      (node (ref "D4") (pin "1") (pinfunction "K_1") (pintype "bidirectional"))
      (node (ref "EPD_C1") (pin "1") (pinfunction "1_1") (pintype "passive"))
      (node (ref "EPD_C10") (pin "1") (pinfunction "1_1") (pintype "passive"))
      (node (ref "EPD_C11") (pin "1") (pinfunction "1_1") (pintype "passive"))
      (node (ref "EPD_C12") (pin "1") (pinfunction "1_1") (pintype "passive"))
      (node (ref "EPD_C2") (pin "1") (pinfunction "1_1") (pintype "passive"))
      (node (ref "EPD_C5") (pin "1") (pinfunction "1_1") (pintype "passive"))
      (node (ref "EPD_C6") (pin "1") (pinfunction "1_1") (pintype "passive"))
      (node (ref "EPD_C7") (pin "1") (pinfunction "1_1") (pintype "passive"))
      (node (ref "EPD_C8") (pin "1") (pinfunction "1_1") (pintype "passive"))
      (node (ref "EPD_C9") (pin "1") (pinfunction "1_1") (pintype "passive"))
      (node (ref "IC1") (pin "D2") (pinfunction "GND_D2") (pintype "bidirectional"))
      (node (ref "IC2") (pin "B1") (pinfunction "IN/TRIG_B1") (pintype "bidirectional"))
      (node (ref "IC2") (pin "B3") (pinfunction "GND_B3") (pintype "bidirectional"))
      (node (ref "IC3") (pin "8") (pinfunction "GNDIO_8") (pintype "bidirectional"))
      (node (ref "IC3") (pin "9") (pinfunction "GND_9") (pintype "bidirectional"))
      (node (ref "IC9") (pin "B1") (pinfunction "VSEL_B1") (pintype "bidirectional"))
      (node (ref "IC9") (pin "C1") (pinfunction "AGND_C1") (pintype "bidirectional"))
      (node (ref "IC9") (pin "C2") (pinfunction "PGND_1_C2") (pintype "bidirectional"))
      (node (ref "IC9") (pin "C3") (pinfunction "PGND_2_C3") (pintype "bidirectional"))
      (node (ref "J1") (pin "17") (pinfunction "17_17") (pintype "bidirectional"))
      (node (ref "J1") (pin "8") (pinfunction "8_8") (pintype "bidirectional"))
      (node (ref "J1") (pin "MP1") (pinfunction "MP1_MP1") (pintype "bidirectional"))
      (node (ref "J1") (pin "MP2") (pinfunction "MP2_MP2") (pintype "bidirectional"))
      (node (ref "J2") (pin "3") (pinfunction "3_3") (pintype "bidirectional"))
      (node (ref "J2") (pin "5") (pinfunction "5_5") (pintype "bidirectional"))
      (node (ref "J4") (pin "A12_B1") (pinfunction "GND_A12_B1") (pintype "power_in"))
      (node (ref "J4") (pin "A1_B12") (pinfunction "GND_A1_B12") (pintype "power_in"))
      (node (ref "J4") (pin "SH1") (pinfunction "SHIELD_SH1") (pintype "passive"))
      (node (ref "J4") (pin "SH2") (pinfunction "SHIELD_SH2") (pintype "passive"))
      (node (ref "J4") (pin "SH3") (pinfunction "SHIELD_SH3") (pintype "passive"))
      (node (ref "J4") (pin "SH4") (pinfunction "SHIELD_SH4") (pintype "passive"))
      (node (ref "R1_USB") (pin "1") (pinfunction "1_1") (pintype "bidirectional"))
      (node (ref "R2_EP_DR") (pin "1") (pinfunction "1_1") (pintype "bidirectional"))
      (node (ref "R2_USB") (pin "2") (pinfunction "2_2") (pintype "bidirectional"))
      (node (ref "R3") (pin "1") (pinfunction "1_1") (pintype "bidirectional"))
      (node (ref "R9") (pin "1") (pinfunction "1_1") (pintype "bidirectional"))
      (node (ref "R_TYPE_SEL") (pin "1") (pinfunction "1_1") (pintype "bidirectional"))
      (node (ref "SJ1") (pin "1") (pinfunction "1_1") (pintype "passive"))
      (node (ref "SW_DN") (pin "1") (pinfunction "1_1") (pintype "passive"))
      (node (ref "SW_ENT") (pin "1") (pinfunction "1_1") (pintype "passive"))
      (node (ref "SW_UP") (pin "1") (pinfunction "1_1") (pintype "passive"))
      (node (ref "TP_BAT_GND") (pin "TP") (pinfunction "TP_TP") (pintype "input"))
      (node (ref "TP_GND") (pin "TP") (pinfunction "TP_TP") (pintype "input"))
      (node (ref "U1") (pin "P$74") (pinfunction "VSS_PAD_P$74") (pintype "bidirectional"))
      (node (ref "U1") (pin "P$75") (pinfunction "VSS_PAD_P$75") (pintype "bidirectional"))
      (node (ref "U1") (pin "P$76") (pinfunction "VSS_PAD_P$76") (pintype "bidirectional"))
      (node (ref "U1") (pin "P$77") (pinfunction "VSS_PAD_P$77") (pintype "bidirectional"))
      (node (ref "U1") (pin "P$78") (pinfunction "VSS_PAD_P$78") (pintype "bidirectional"))
      (node (ref "U1") (pin "P$79") (pinfunction "VSS_PAD_P$79") (pintype "bidirectional"))
      (node (ref "U1") (pin "P$80") (pinfunction "VSS_PAD_P$80") (pintype "bidirectional"))
      (node (ref "U1") (pin "P$81") (pinfunction "VSS_PAD_P$81") (pintype "bidirectional"))
      (node (ref "U1") (pin "P$82") (pinfunction "VSS_PAD_P$82") (pintype "bidirectional"))
      (node (ref "U1") (pin "P$83") (pinfunction "VSS_PAD_P$83") (pintype "bidirectional"))
      (node (ref "U1") (pin "P$84") (pinfunction "VSS_PAD_P$84") (pintype "bidirectional"))
      (node (ref "U1") (pin "P$85") (pinfunction "VSS_PAD_P$85") (pintype "bidirectional"))
      (node (ref "U1") (pin "P$86") (pinfunction "VSS_PAD_P$86") (pintype "bidirectional"))
      (node (ref "U1") (pin "P$87") (pinfunction "VSS_PAD_P$87") (pintype "bidirectional"))
      (node (ref "U1") (pin "P$88") (pinfunction "VSS_PAD_P$88") (pintype "bidirectional"))
      (node (ref "U1") (pin "P$89") (pinfunction "VSS_PAD_P$89") (pintype "bidirectional"))
      (node (ref "U1") (pin "P$90") (pinfunction "VSS_PAD_P$90") (pintype "bidirectional"))
      (node (ref "U1") (pin "P$B7") (pinfunction "VSS_P$B7") (pintype "power_in"))
      (node (ref "U1") (pin "P$F23") (pinfunction "VSS_PA_P$F23") (pintype "bidirectional"))
      (node (ref "U3") (pin "1") (pinfunction "CTG_1") (pintype "power_in"))
      (node (ref "U3") (pin "4") (pinfunction "GND_4") (pintype "power_in"))
      (node (ref "U3") (pin "6") (pinfunction "QSTRT_6") (pintype "input"))
      (node (ref "U3") (pin "9") (pinfunction "EP_9") (pintype "power_in"))
      (node (ref "X1") (pin "2") (pinfunction "2_2") (pintype "passive"))
      (node (ref "X1") (pin "4") (pinfunction "4_4") (pintype "passive"))
    )
    (net (code "14") (name "HAPTIC_EN") (class "Default")
      (node (ref "IC2") (pin "A1") (pinfunction "EN_A1") (pintype "bidirectional"))
      (node (ref "U1") (pin "P$U1") (pinfunction "P0.12_P$U1") (pintype "bidirectional"))
    )
    (net (code "15") (name "IMU_INT1") (class "Default")
      (node (ref "IC3") (pin "5") (pinfunction "INT1_5") (pintype "bidirectional"))
      (node (ref "U1") (pin "P$N1") (pinfunction "P0.08_P$N1") (pintype "bidirectional"))
    )
    (net (code "16") (name "IMU_INT2") (class "Default")
      (node (ref "IC3") (pin "6") (pinfunction "INT2_6") (pintype "bidirectional"))
      (node (ref "U1") (pin "P$P2") (pinfunction "P1.08_P$P2") (pintype "bidirectional"))
    )
    (net (code "17") (name "LX1") (class "Default")
      (node (ref "IC9") (pin "B2") (pinfunction "SW1_1_B2") (pintype "bidirectional"))
      (node (ref "IC9") (pin "B3") (pinfunction "SW1_2_B3") (pintype "bidirectional"))
      (node (ref "L7") (pin "1") (pinfunction "1_1") (pintype "bidirectional"))
    )
    (net (code "18") (name "LX2") (class "Default")
      (node (ref "IC9") (pin "D2") (pinfunction "SW2_1_D2") (pintype "bidirectional"))
      (node (ref "IC9") (pin "D3") (pinfunction "SW2_2_D3") (pintype "bidirectional"))
      (node (ref "L7") (pin "2") (pinfunction "2_2") (pintype "bidirectional"))
    )
    (net (code "19") (name "MOSI") (class "Default")
      (node (ref "J1") (pin "14") (pinfunction "14_14") (pintype "bidirectional"))
      (node (ref "U1") (pin "P$B13") (pinfunction "P0.03/AIN1_P$B13") (pintype "bidirectional"))
    )
    (net (code "20") (name "Net-(ANT1-FEED)") (class "Default")
      (node (ref "ANT1") (pin "1") (pinfunction "FEED_1") (pintype "input"))
      (node (ref "C22") (pin "1") (pinfunction "1_1") (pintype "passive"))
      (node (ref "C4") (pin "1") (pinfunction "1_1") (pintype "passive"))
      (node (ref "L1") (pin "2") (pinfunction "2_2") (pintype "passive"))
    )
    (net (code "21") (name "Net-(D2-K)") (class "Default")
      (node (ref "C2-EP-DR") (pin "1") (pinfunction "1_1") (pintype "passive"))
      (node (ref "D2") (pin "1") (pinfunction "K_1") (pintype "bidirectional"))
      (node (ref "D4") (pin "2") (pinfunction "A_2") (pintype "bidirectional"))
    )
    (net (code "22") (name "Net-(D5-A)") (class "Default")
      (node (ref "C2-EP-DR") (pin "2") (pinfunction "2_2") (pintype "passive"))
      (node (ref "D5") (pin "2") (pinfunction "A_2") (pintype "bidirectional"))
      (node (ref "L5") (pin "1") (pinfunction "1_1") (pintype "passive"))
      (node (ref "Q3") (pin "3") (pinfunction "D_3") (pintype "bidirectional"))
    )
    (net (code "23") (name "Net-(EPD_C1-Pad2)") (class "Default")
      (node (ref "EPD_C1") (pin "2") (pinfunction "2_2") (pintype "passive"))
      (node (ref "J1") (pin "5") (pinfunction "5_5") (pintype "bidirectional"))
    )
    (net (code "24") (name "Net-(EPD_C2-Pad2)") (class "Default")
      (node (ref "EPD_C2") (pin "2") (pinfunction "2_2") (pintype "passive"))
      (node (ref "J1") (pin "4") (pinfunction "4_4") (pintype "bidirectional"))
    )
    (net (code "25") (name "Net-(EPD_C6-Pad2)") (class "Default")
      (node (ref "EPD_C6") (pin "2") (pinfunction "2_2") (pintype "passive"))
      (node (ref "J1") (pin "18") (pinfunction "18_18") (pintype "bidirectional"))
    )
    (net (code "26") (name "Net-(EPD_C7-Pad2)") (class "Default")
      (node (ref "EPD_C7") (pin "2") (pinfunction "2_2") (pintype "passive"))
      (node (ref "J1") (pin "19") (pinfunction "19_19") (pintype "bidirectional"))
    )
    (net (code "27") (name "Net-(EPD_C8-Pad2)") (class "Default")
      (node (ref "EPD_C8") (pin "2") (pinfunction "2_2") (pintype "passive"))
      (node (ref "J1") (pin "20") (pinfunction "20_20") (pintype "bidirectional"))
    )
    (net (code "28") (name "Net-(EPD_C10-Pad2)") (class "Default")
      (node (ref "EPD_C10") (pin "2") (pinfunction "2_2") (pintype "passive"))
      (node (ref "J1") (pin "22") (pinfunction "22_22") (pintype "bidirectional"))
    )
    (net (code "29") (name "Net-(EPD_C12-Pad2)") (class "Default")
      (node (ref "EPD_C12") (pin "2") (pinfunction "2_2") (pintype "passive"))
      (node (ref "J1") (pin "24") (pinfunction "24_24") (pintype "bidirectional"))
    )
    (net (code "30") (name "Net-(IC1-TS{slash}MR)") (class "Default")
      (node (ref "IC1") (pin "D1") (pinfunction "TS/MR_D1") (pintype "bidirectional"))
      (node (ref "R9") (pin "2") (pinfunction "2_2") (pintype "bidirectional"))
    )
    (net (code "31") (name "Net-(IC2-REG)") (class "Default")
      (node (ref "C32") (pin "2") (pinfunction "2_2") (pintype "passive"))
      (node (ref "IC2") (pin "A2") (pinfunction "REG_A2") (pintype "bidirectional"))
    )
    (net (code "32") (name "Net-(IC3-SDO)") (class "Default")
      (node (ref "IC3") (pin "1") (pinfunction "SDO_1") (pintype "bidirectional"))
      (node (ref "R3") (pin "2") (pinfunction "2_2") (pintype "bidirectional"))
    )
    (net (code "33") (name "Net-(IC9-SCL)") (class "Default")
      (node (ref "IC9") (pin "D1") (pinfunction "SCL_D1") (pintype "bidirectional"))
      (node (ref "R4") (pin "2") (pinfunction "2_2") (pintype "bidirectional"))
    )
    (net (code "34") (name "Net-(IC9-SDA)") (class "Default")
      (node (ref "IC9") (pin "E1") (pinfunction "SDA_E1") (pintype "bidirectional"))
      (node (ref "R2") (pin "2") (pinfunction "2_2") (pintype "bidirectional"))
    )
    (net (code "35") (name "Net-(J4-CC1)") (class "Default")
      (node (ref "J4") (pin "A5") (pinfunction "CC1_A5") (pintype "bidirectional"))
      (node (ref "R1_USB") (pin "2") (pinfunction "2_2") (pintype "bidirectional"))
    )
    (net (code "36") (name "Net-(J4-CC2)") (class "Default")
      (node (ref "J4") (pin "B5") (pinfunction "CC2_B5") (pintype "bidirectional"))
      (node (ref "R2_USB") (pin "1") (pinfunction "1_1") (pintype "bidirectional"))
    )
    (net (code "37") (name "Net-(L2-Pad2)") (class "Default")
      (node (ref "L2") (pin "2") (pinfunction "2_2") (pintype "passive"))
      (node (ref "L3") (pin "1") (pinfunction "1_1") (pintype "passive"))
    )
    (net (code "38") (name "Net-(R1_EP_DR-Pad1)") (class "Default")
      (node (ref "R1_EP_DR") (pin "1") (pinfunction "1_1") (pintype "bidirectional"))
      (node (ref "R_TYPE_SEL") (pin "2") (pinfunction "2_2") (pintype "bidirectional"))
      (node (ref "SJ1") (pin "2") (pinfunction "2_2") (pintype "passive"))
    )
    (net (code "39") (name "Net-(U1-ANT)") (class "Default")
      (node (ref "C3") (pin "1") (pinfunction "1_1") (pintype "passive"))
      (node (ref "L1") (pin "1") (pinfunction "1_1") (pintype "passive"))
      (node (ref "U1") (pin "P$H23") (pinfunction "ANT_P$H23") (pintype "bidirectional"))
    )
    (net (code "40") (name "Net-(U1-DCC)") (class "Default")
      (node (ref "L2") (pin "1") (pinfunction "1_1") (pintype "passive"))
      (node (ref "U1") (pin "P$B3") (pinfunction "DCC_P$B3") (pintype "output"))
    )
    (net (code "41") (name "Net-(U1-DEC1)") (class "Default")
      (node (ref "C5") (pin "1") (pinfunction "1_1") (pintype "passive"))
      (node (ref "U1") (pin "P$C1") (pinfunction "DEC1_P$C1") (pintype "power_in"))
    )
    (net (code "42") (name "Net-(U1-DEC2)") (class "Default")
      (node (ref "C13") (pin "1") (pinfunction "1_1") (pintype "passive"))
      (node (ref "U1") (pin "P$A18") (pinfunction "DEC2_P$A18") (pintype "bidirectional"))
    )
    (net (code "43") (name "Net-(U1-DEC3)") (class "Default")
      (node (ref "C11") (pin "1") (pinfunction "1_1") (pintype "passive"))
      (node (ref "U1") (pin "P$D23") (pinfunction "DEC3_P$D23") (pintype "bidirectional"))
    )
    (net (code "44") (name "Net-(U1-DEC3V3)") (class "Default")
      (node (ref "C20") (pin "1") (pinfunction "1_1") (pintype "passive"))
      (node (ref "U1") (pin "P$AC5") (pinfunction "DEC3V3_P$AC5") (pintype "bidirectional"))
    )
    (net (code "45") (name "Net-(U1-DEC4)") (class "Default")
      (node (ref "C10") (pin "1") (pinfunction "1_1") (pintype "passive"))
      (node (ref "C15") (pin "1") (pinfunction "1_1") (pintype "passive"))
      (node (ref "C16") (pin "1") (pinfunction "1_1") (pintype "passive"))
      (node (ref "L3") (pin "2") (pinfunction "2_2") (pintype "passive"))
      (node (ref "U1") (pin "P$B5") (pinfunction "DEC4_P$B5") (pintype "power_in"))
      (node (ref "U1") (pin "P$E24") (pinfunction "DEC6_P$E24") (pintype "bidirectional"))
    )
    (net (code "46") (name "Net-(U1-DEC5)") (class "Default")
      (node (ref "C9") (pin "1") (pinfunction "1_1") (pintype "passive"))
      (node (ref "U1") (pin "P$N24") (pinfunction "DEC5_P$N24") (pintype "bidirectional"))
    )
    (net (code "47") (name "Net-(U1-P0.00{slash}XL1)") (class "Default")
      (node (ref "C17") (pin "2") (pinfunction "2_2") (pintype "passive"))
      (node (ref "U1") (pin "P$D2") (pinfunction "P0.00/XL1_P$D2") (pintype "bidirectional"))
      (node (ref "X2") (pin "1") (pinfunction "1_1") (pintype "passive"))
    )
    (net (code "48") (name "Net-(U1-P0.01{slash}XL2)") (class "Default")
      (node (ref "C18") (pin "2") (pinfunction "2_2") (pintype "passive"))
      (node (ref "U1") (pin "P$F2") (pinfunction "P0.01/XL2_P$F2") (pintype "bidirectional"))
      (node (ref "X2") (pin "2") (pinfunction "2_2") (pintype "passive"))
    )
    (net (code "49") (name "Net-(U1-XC1)") (class "Default")
      (node (ref "C1") (pin "1") (pinfunction "1_1") (pintype "passive"))
      (node (ref "U1") (pin "P$B24") (pinfunction "XC1_P$B24") (pintype "input"))
      (node (ref "X1") (pin "1") (pinfunction "1_1") (pintype "passive"))
    )
    (net (code "50") (name "Net-(U1-XC2)") (class "Default")
      (node (ref "C2") (pin "1") (pinfunction "1_1") (pintype "passive"))
      (node (ref "U1") (pin "P$A23") (pinfunction "XC2_P$A23") (pintype "output"))
      (node (ref "X1") (pin "3") (pinfunction "3_3") (pintype "passive"))
    )
    (net (code "51") (name "OUT+") (class "Default")
      (node (ref "IC2") (pin "A3") (pinfunction "OUT+_A3") (pintype "bidirectional"))
      (node (ref "TP_OP") (pin "TP") (pinfunction "TP_TP") (pintype "input"))
    )
    (net (code "52") (name "OUT-") (class "Default")
      (node (ref "IC2") (pin "C3") (pinfunction "OUT-_C3") (pintype "bidirectional"))
      (node (ref "TP_ON") (pin "TP") (pinfunction "TP_TP") (pintype "input"))
    )
    (net (code "53") (name "P0.04") (class "Default")
      (node (ref "U1") (pin "P$J1") (pinfunction "P0.04/AIN2_P$J1") (pintype "bidirectional"))
    )
    (net (code "54") (name "P0.09") (class "Default")
      (node (ref "U1") (pin "P$L24") (pinfunction "P0.09/NFC1_P$L24") (pintype "bidirectional"))
    )
    (net (code "55") (name "P0.13") (class "Default")
      (node (ref "C30") (pin "2") (pinfunction "2_2") (pintype "passive"))
      (node (ref "R5") (pin "1") (pinfunction "1_1") (pintype "bidirectional"))
      (node (ref "SW_UP") (pin "2") (pinfunction "2_2") (pintype "passive"))
      (node (ref "U1") (pin "P$AD8") (pinfunction "P0.13_P$AD8") (pintype "bidirectional"))
    )
    (net (code "56") (name "P0.14") (class "Default")
      (node (ref "C31") (pin "2") (pinfunction "2_2") (pintype "passive"))
      (node (ref "R8") (pin "1") (pinfunction "1_1") (pintype "bidirectional"))
      (node (ref "SW_ENT") (pin "2") (pinfunction "2_2") (pintype "passive"))
      (node (ref "U1") (pin "P$AC9") (pinfunction "P0.14_P$AC9") (pintype "bidirectional"))
    )
    (net (code "57") (name "P0.19") (class "Default")
      (node (ref "U1") (pin "P$AC15") (pinfunction "P0.19_P$AC15") (pintype "bidirectional"))
    )
    (net (code "58") (name "P0.20") (class "Default")
      (node (ref "U1") (pin "P$AD16") (pinfunction "P0.20_P$AD16") (pintype "bidirectional"))
    )
    (net (code "59") (name "P0.21") (class "Default")
      (node (ref "U1") (pin "P$AC17") (pinfunction "P0.21_P$AC17") (pintype "bidirectional"))
    )
    (net (code "60") (name "P0.22") (class "Default")
      (node (ref "U1") (pin "P$AD18") (pinfunction "P0.22_P$AD18") (pintype "bidirectional"))
    )
    (net (code "61") (name "P0.23") (class "Default")
      (node (ref "U1") (pin "P$AC19") (pinfunction "P0.23_P$AC19") (pintype "bidirectional"))
    )
    (net (code "62") (name "P0.24") (class "Default")
      (node (ref "U1") (pin "P$AD20") (pinfunction "P0.24_P$AD20") (pintype "bidirectional"))
    )
    (net (code "63") (name "P0.25") (class "Default")
      (node (ref "U1") (pin "P$AC21") (pinfunction "P0.25_P$AC21") (pintype "bidirectional"))
    )
    (net (code "64") (name "P0.26") (class "Default")
      (node (ref "U1") (pin "P$G1") (pinfunction "P0.26_P$G1") (pintype "bidirectional"))
    )
    (net (code "65") (name "P0.27") (class "Default")
      (node (ref "U1") (pin "P$H2") (pinfunction "P0.27_P$H2") (pintype "bidirectional"))
    )
    (net (code "66") (name "P0.28") (class "Default")
      (node (ref "U1") (pin "P$B11") (pinfunction "P0.28/AIN4_P$B11") (pintype "bidirectional"))
    )
    (net (code "67") (name "P0.29") (class "Default")
      (node (ref "U1") (pin "P$A10") (pinfunction "P0.29/AIN5_P$A10") (pintype "bidirectional"))
    )
    (net (code "68") (name "P0.30") (class "Default")
      (node (ref "U1") (pin "P$B9") (pinfunction "P0.30/AIN6_P$B9") (pintype "bidirectional"))
    )
    (net (code "69") (name "P0.31") (class "Default")
      (node (ref "U1") (pin "P$A8") (pinfunction "P0.31/AIN7_P$A8") (pintype "bidirectional"))
    )
    (net (code "70") (name "P1.01") (class "Default")
      (node (ref "DMG2305UX-7") (pin "1") (pinfunction "G_1") (pintype "bidirectional"))
      (node (ref "R_PWR_EPD") (pin "1") (pinfunction "1_1") (pintype "bidirectional"))
      (node (ref "U1") (pin "P$Y23") (pinfunction "P1.01_P$Y23") (pintype "bidirectional"))
    )
    (net (code "71") (name "P1.02") (class "Default")
      (node (ref "C29") (pin "2") (pinfunction "2_2") (pintype "passive"))
      (node (ref "R7") (pin "1") (pinfunction "1_1") (pintype "bidirectional"))
      (node (ref "SW_DN") (pin "2") (pinfunction "2_2") (pintype "passive"))
      (node (ref "U1") (pin "P$W24") (pinfunction "P1.02_P$W24") (pintype "bidirectional"))
    )
    (net (code "72") (name "P1.03") (class "Default")
      (node (ref "U1") (pin "P$V23") (pinfunction "P1.03_P$V23") (pintype "bidirectional"))
    )
    (net (code "73") (name "P1.04") (class "Default")
      (node (ref "U1") (pin "P$U24") (pinfunction "P1.04_P$U24") (pintype "bidirectional"))
    )
    (net (code "74") (name "P1.05") (class "Default")
      (node (ref "U1") (pin "P$T23") (pinfunction "P1.05_P$T23") (pintype "bidirectional"))
    )
    (net (code "75") (name "P1.06") (class "Default")
      (node (ref "U1") (pin "P$R24") (pinfunction "P1.06_P$R24") (pintype "bidirectional"))
    )
    (net (code "76") (name "P1.07") (class "Default")
      (node (ref "U1") (pin "P$P23") (pinfunction "P1.07_P$P23") (pintype "bidirectional"))
    )
    (net (code "77") (name "P1.09") (class "Default")
      (node (ref "U1") (pin "P$R1") (pinfunction "P1.09_P$R1") (pintype "bidirectional"))
    )
    (net (code "78") (name "P1.10") (class "Default")
      (node (ref "U1") (pin "P$A20") (pinfunction "P1.10_P$A20") (pintype "bidirectional"))
    )
    (net (code "79") (name "P1.11") (class "Default")
      (node (ref "U1") (pin "P$B19") (pinfunction "P1.11_P$B19") (pintype "bidirectional"))
    )
    (net (code "80") (name "P1.12") (class "Default")
      (node (ref "U1") (pin "P$B17") (pinfunction "P1.12_P$B17") (pintype "bidirectional"))
    )
    (net (code "81") (name "P1.13") (class "Default")
      (node (ref "U1") (pin "P$A16") (pinfunction "P1.13_P$A16") (pintype "bidirectional"))
    )
    (net (code "82") (name "P1.14") (class "Default")
      (node (ref "U1") (pin "P$B15") (pinfunction "P1.14_P$B15") (pintype "bidirectional"))
    )
    (net (code "83") (name "P1.15") (class "Default")
      (node (ref "U1") (pin "P$A14") (pinfunction "P1.15_P$A14") (pintype "bidirectional"))
    )
    (net (code "84") (name "PMIC_INT") (class "Default")
      (node (ref "IC1") (pin "A1") (pinfunction "~{INT}_A1") (pintype "bidirectional"))
      (node (ref "U1") (pin "P$T2") (pinfunction "P0.11_P$T2") (pintype "bidirectional"))
    )
    (net (code "85") (name "PREVGH") (class "Default")
      (node (ref "D5") (pin "1") (pinfunction "K_1") (pintype "bidirectional"))
      (node (ref "EPD_C9") (pin "2") (pinfunction "2_2") (pintype "passive"))
      (node (ref "J1") (pin "21") (pinfunction "21_21") (pintype "bidirectional"))
    )
    (net (code "86") (name "PREVGL") (class "Default")
      (node (ref "D2") (pin "2") (pinfunction "A_2") (pintype "bidirectional"))
      (node (ref "EPD_C11") (pin "2") (pinfunction "2_2") (pintype "passive"))
      (node (ref "J1") (pin "23") (pinfunction "23_23") (pintype "bidirectional"))
    )
    (net (code "87") (name "RESE") (class "Default")
      (node (ref "J1") (pin "3") (pinfunction "3_3") (pintype "bidirectional"))
      (node (ref "Q3") (pin "2") (pinfunction "S_2") (pintype "bidirectional"))
      (node (ref "R1_EP_DR") (pin "2") (pinfunction "2_2") (pintype "bidirectional"))
    )
    (net (code "88") (name "RESET") (class "Default")
      (node (ref "J2") (pin "6") (pinfunction "6_6") (pintype "bidirectional"))
      (node (ref "TP_RESET") (pin "TP") (pinfunction "TP_TP") (pintype "input"))
      (node (ref "U1") (pin "P$AC13") (pinfunction "P0.18/RESET_P$AC13") (pintype "bidirectional"))
    )
    (net (code "89") (name "SCK") (class "Default")
      (node (ref "J1") (pin "13") (pinfunction "13_13") (pintype "bidirectional"))
      (node (ref "U1") (pin "P$A12") (pinfunction "P0.02/AIN0_P$A12") (pintype "bidirectional"))
    )
    (net (code "90") (name "SCL") (class "Default")
      (node (ref "IC1") (pin "B1") (pinfunction "SCL_B1") (pintype "bidirectional"))
      (node (ref "IC2") (pin "C1") (pinfunction "SCL_C1") (pintype "bidirectional"))
      (node (ref "IC3") (pin "12") (pinfunction "SCX_12") (pintype "bidirectional"))
      (node (ref "R17") (pin "2") (pinfunction "2_2") (pintype "bidirectional"))
      (node (ref "R2") (pin "1") (pinfunction "1_1") (pintype "bidirectional"))
      (node (ref "R4") (pin "1") (pinfunction "1_1") (pintype "bidirectional"))
      (node (ref "TP_SCL") (pin "TP") (pinfunction "TP_TP") (pintype "input"))
      (node (ref "U1") (pin "P$M2") (pinfunction "P0.07_P$M2") (pintype "bidirectional"))
      (node (ref "U3") (pin "7") (pinfunction "SCL_7") (pintype "input"))
    )
    (net (code "91") (name "SDA") (class "Default")
      (node (ref "IC1") (pin "C1") (pinfunction "SDA_C1") (pintype "bidirectional"))
      (node (ref "IC2") (pin "B2") (pinfunction "SDA_B2") (pintype "bidirectional"))
      (node (ref "IC3") (pin "2") (pinfunction "SDX_2") (pintype "bidirectional"))
      (node (ref "R18") (pin "2") (pinfunction "2_2") (pintype "bidirectional"))
      (node (ref "TP_SDA") (pin "TP") (pinfunction "TP_TP") (pintype "input"))
      (node (ref "U1") (pin "P$L1") (pinfunction "P0.06_P$L1") (pintype "bidirectional"))
      (node (ref "U3") (pin "8") (pinfunction "SDA_8") (pintype "bidirectional"))
    )
    (net (code "92") (name "SWDCLK") (class "Default")
      (node (ref "J2") (pin "4") (pinfunction "4_4") (pintype "bidirectional"))
      (node (ref "TP_SWDCLK") (pin "TP") (pinfunction "TP_TP") (pintype "input"))
      (node (ref "U1") (pin "P$AA24") (pinfunction "SWDCLK_P$AA24") (pintype "input"))
    )
    (net (code "93") (name "SWDIO") (class "Default")
      (node (ref "J2") (pin "2") (pinfunction "2_2") (pintype "bidirectional"))
      (node (ref "TP_SWDIO") (pin "TP") (pinfunction "TP_TP") (pintype "input"))
      (node (ref "U1") (pin "P$AC24") (pinfunction "SWDIO_P$AC24") (pintype "bidirectional"))
    )
    (net (code "94") (name "SWO") (class "Default")
      (node (ref "TP_SWO") (pin "TP") (pinfunction "TP_TP") (pintype "input"))
      (node (ref "U1") (pin "P$AD22") (pinfunction "P1.00_P$AD22") (pintype "bidirectional"))
    )
    (net (code "95") (name "VBAT") (class "Default")
      (node (ref "C27") (pin "2") (pinfunction "2_2") (pintype "passive"))
      (node (ref "C37") (pin "2") (pinfunction "2_2") (pintype "passive"))
      (node (ref "IC1") (pin "C2") (pinfunction "BAT_C2") (pintype "bidirectional"))
      (node (ref "TP_VBAT") (pin "TP") (pinfunction "TP_TP") (pintype "input"))
      (node (ref "U3") (pin "2") (pinfunction "CELL_2") (pintype "power_in"))
      (node (ref "U3") (pin "3") (pinfunction "VDD_3") (pintype "power_in"))
    )
    (net (code "96") (name "VBUS") (class "Default")
      (node (ref "C21") (pin "1") (pinfunction "1_1") (pintype "passive"))
      (node (ref "C38") (pin "2") (pinfunction "2_2") (pintype "passive"))
      (node (ref "C42") (pin "1") (pinfunction "1_1") (pintype "passive"))
      (node (ref "C43") (pin "1") (pinfunction "1_1") (pintype "passive"))
      (node (ref "D3") (pin "5") (pinfunction "VBUS_5") (pintype "bidirectional"))
      (node (ref "IC1") (pin "A2") (pinfunction "IN_A2") (pintype "bidirectional"))
      (node (ref "J4") (pin "A4_B9") (pinfunction "VBUS_A4_B9") (pintype "power_in"))
      (node (ref "J4") (pin "A9_B4") (pinfunction "VBUS_A9_B4") (pintype "power_in"))
      (node (ref "U1") (pin "P$AD2") (pinfunction "VBUS_P$AD2") (pintype "power_in"))
    )
    (net (code "97") (name "VREG") (class "Default")
      (node (ref "C23") (pin "2") (pinfunction "2_2") (pintype "passive"))
      (node (ref "C24") (pin "2") (pinfunction "2_2") (pintype "passive"))
      (node (ref "C39") (pin "1") (pinfunction "1_1") (pintype "passive"))
      (node (ref "IC1") (pin "B2") (pinfunction "SYS_B2") (pintype "bidirectional"))
      (node (ref "IC9") (pin "A1") (pinfunction "EN_A1") (pintype "bidirectional"))
      (node (ref "IC9") (pin "A2") (pinfunction "VIN_1_A2") (pintype "bidirectional"))
      (node (ref "IC9") (pin "A3") (pinfunction "VIN_2_A3") (pintype "bidirectional"))
      (node (ref "TP_VREG") (pin "TP") (pinfunction "TP_TP") (pintype "input"))
    )
    (net (code "98") (name "unconnected-(ANT1-NC-Pad2)") (class "Default")
      (node (ref "ANT1") (pin "2") (pinfunction "NC_2") (pintype "no_connect"))
    )
    (net (code "99") (name "unconnected-(IC3-ASCL-Pad11)") (class "Default")
      (node (ref "IC3") (pin "11") (pinfunction "ASCL_11") (pintype "bidirectional"))
    )
    (net (code "100") (name "unconnected-(IC3-ASDA-Pad4)") (class "Default")
      (node (ref "IC3") (pin "4") (pinfunction "ASDA_4") (pintype "bidirectional"))
    )
    (net (code "101") (name "unconnected-(J1-Pad1)") (class "Default")
      (node (ref "J1") (pin "1") (pinfunction "1_1") (pintype "bidirectional"))
    )
    (net (code "102") (name "unconnected-(J1-Pad6)") (class "Default")
      (node (ref "J1") (pin "6") (pinfunction "6_6") (pintype "bidirectional"))
    )
    (net (code "103") (name "unconnected-(J1-Pad7)") (class "Default")
      (node (ref "J1") (pin "7") (pinfunction "7_7") (pintype "bidirectional"))
    )
    (net (code "104") (name "unconnected-(J4-SBU1-PadA8)") (class "Default")
      (node (ref "J4") (pin "A8") (pinfunction "SBU1_A8") (pintype "bidirectional"))
    )
    (net (code "105") (name "unconnected-(J4-SBU2-PadB8)") (class "Default")
      (node (ref "J4") (pin "B8") (pinfunction "SBU2_B8") (pintype "bidirectional"))
    )
    (net (code "106") (name "unconnected-(U1-DCCH-PadP$AB2)") (class "Default")
      (node (ref "U1") (pin "P$AB2") (pinfunction "DCCH_P$AB2") (pintype "bidirectional"))
    )
  )
)
